# stokes_polarimeter_oled.net
KiCad netlist of a schematic drawn in EAGLE
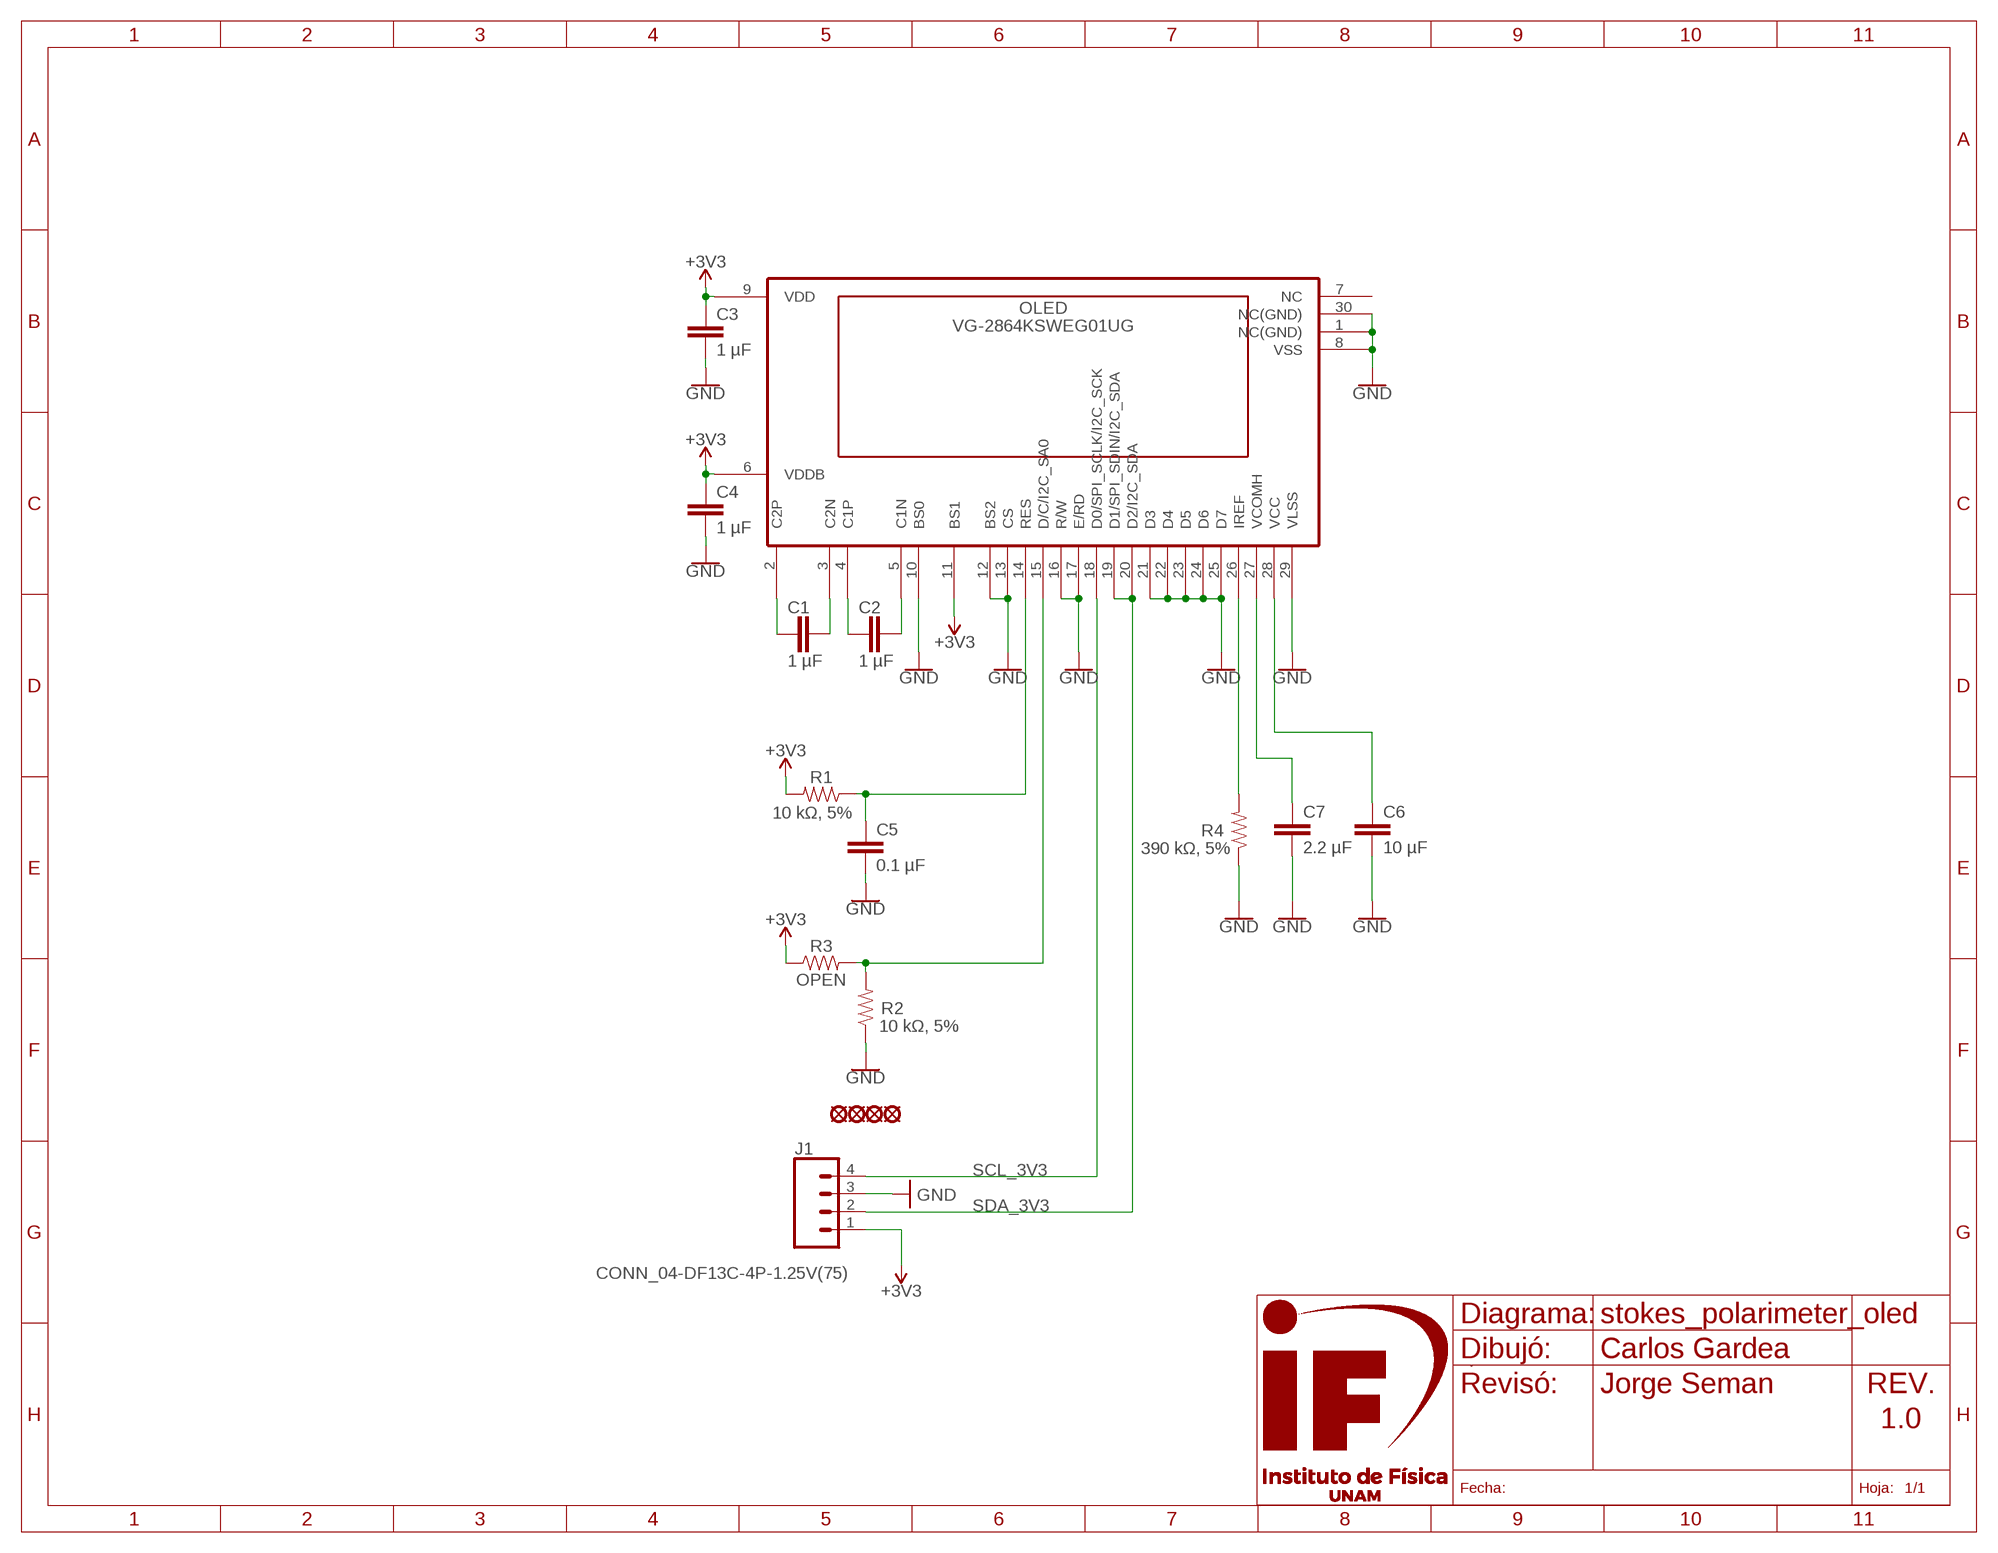
[diagram p0: schematic, sheet 1]

(export (version "E")
  (design (tool "Eeschema 10.0.6"))
  (components
    (comp (ref "C1")
      (value "1 µF")
      (footprint "eagle-import:C1206")
      (fields (field (name "MFR") "KEMET"))
      (libsource (lib "eagle-import") (part "1µF-C1206C105K3RACTU"))
    )
    (comp (ref "C2")
      (value "1 µF")
      (footprint "eagle-import:C1206")
      (fields (field (name "MFR") "KEMET"))
      (libsource (lib "eagle-import") (part "1µF-C1206C105K3RACTU"))
    )
    (comp (ref "C3")
      (value "1 µF")
      (footprint "eagle-import:C1206")
      (fields (field (name "MFR") "KEMET"))
      (libsource (lib "eagle-import") (part "1µF-C1206C105K3RACTU"))
    )
    (comp (ref "C4")
      (value "1 µF")
      (footprint "eagle-import:C1206")
      (fields (field (name "MFR") "KEMET"))
      (libsource (lib "eagle-import") (part "1µF-C1206C105K3RACTU"))
    )
    (comp (ref "C5")
      (value "0.1 µF")
      (footprint "eagle-import:C1206")
      (fields (field (name "MFR") "KEMET"))
      (libsource (lib "eagle-import") (part "0.1µF-C1206C104J1RACTU"))
    )
    (comp (ref "C6")
      (value "10 µF")
      (footprint "eagle-import:C1206")
      (fields (field (name "MFR") "KEMET"))
      (libsource (lib "eagle-import") (part "10µF-C1206C106K4PACTU"))
    )
    (comp (ref "C7")
      (value "2.2 µF")
      (footprint "eagle-import:C1206")
      (fields (field (name "MFR") "KEMET"))
      (libsource (lib "eagle-import") (part "2.2µF-C1206C225K4PACTU"))
    )
    (comp (ref "H5")
      (value "HOLE-M2.5")
      (footprint "eagle-import:HOLE_2.5")
      (libsource (lib "eagle-import") (part "HOLE-M2.5"))
    )
    (comp (ref "H6")
      (value "HOLE-M2.5")
      (footprint "eagle-import:HOLE_2.5")
      (libsource (lib "eagle-import") (part "HOLE-M2.5"))
    )
    (comp (ref "H7")
      (value "HOLE-M2.5")
      (footprint "eagle-import:HOLE_2.5")
      (libsource (lib "eagle-import") (part "HOLE-M2.5"))
    )
    (comp (ref "H8")
      (value "HOLE-M2.5")
      (footprint "eagle-import:HOLE_2.5")
      (libsource (lib "eagle-import") (part "HOLE-M2.5"))
    )
    (comp (ref "J1")
      (value "CONN_04-DF13C-4P-1.25V(75)")
      (footprint "eagle-import:DF13C4P125V")
      (fields (field (name "MFR") "Hirose Connector"))
      (libsource (lib "eagle-import") (part "CONN_04-DF13C-4P-1.25V(75)"))
    )
    (comp (ref "OLED")
      (value "VG-2864KSWEG01UG")
      (footprint "eagle-import:UG-2864HSWEG01")
      (libsource (lib "eagle-import") (part "VG-2864KSWEG01UG"))
    )
    (comp (ref "R1")
      (value "10 kΩ, 5%")
      (footprint "eagle-import:R1206")
      (fields (field (name "MFR") "Yageo"))
      (libsource (lib "eagle-import") (part "10KΩ-RC1206JR-0710KL"))
    )
    (comp (ref "R2")
      (value "10 kΩ, 5%")
      (footprint "eagle-import:R1206")
      (fields (field (name "MFR") "Yageo"))
      (libsource (lib "eagle-import") (part "10KΩ-RC1206JR-0710KL"))
    )
    (comp (ref "R3")
      (value "OPEN")
      (footprint "eagle-import:R1206_OPEN")
      (fields (field (name "MFR") "NA"))
      (libsource (lib "eagle-import") (part "OPEN"))
    )
    (comp (ref "R4")
      (value "390 kΩ, 5%")
      (footprint "eagle-import:R1206")
      (fields (field (name "MFR") "Yageo"))
      (libsource (lib "eagle-import") (part "390KΩ-RC1206JR-07390KL"))
    )
    (comp (ref "U$1")
      (value "IFUNAM_FRAME_LETTER_HNONE")
      (footprint "eagle-import:NONE")
      (fields
        (field (name "AUTHOR") "Carlos Gardea")
        (field (name "REVISOR") "Jorge Seman")
        (field (name "author") "author")
      )
      (libsource (lib "eagle-import") (part "IFUNAM_FRAME_LETTER_HNONE"))
    )
  )
  (nets
    (net (code "1") (name "+3V3") (class "Default")
      (node (ref "C3") (pin "1") (pinfunction "1_1") (pintype "passive"))
      (node (ref "C4") (pin "1") (pinfunction "1_1") (pintype "passive"))
      (node (ref "J1") (pin "1") (pinfunction "1_1") (pintype "passive"))
      (node (ref "OLED") (pin "11") (pinfunction "BS1_11") (pintype "passive"))
      (node (ref "OLED") (pin "6") (pinfunction "VDDB_6") (pintype "passive"))
      (node (ref "OLED") (pin "9") (pinfunction "VDD_9") (pintype "passive"))
      (node (ref "R1") (pin "2") (pinfunction "2_2") (pintype "passive"))
      (node (ref "R3") (pin "1") (pinfunction "1_1") (pintype "passive"))
    )
    (net (code "2") (name "/SCL_3V3") (class "Default")
      (node (ref "J1") (pin "4") (pinfunction "4_4") (pintype "passive"))
      (node (ref "OLED") (pin "18") (pinfunction "D0/SPI_SCLK/I2C_SCK_18") (pintype "passive"))
    )
    (net (code "3") (name "/SDA_3V3") (class "Default")
      (node (ref "J1") (pin "2") (pinfunction "2_2") (pintype "passive"))
      (node (ref "OLED") (pin "19") (pinfunction "D1/SPI_SDIN/I2C_SDA_19") (pintype "passive"))
      (node (ref "OLED") (pin "20") (pinfunction "D2/I2C_SDA_20") (pintype "passive"))
    )
    (net (code "4") (name "GND") (class "Default")
      (node (ref "C3") (pin "2") (pinfunction "2_2") (pintype "passive"))
      (node (ref "C4") (pin "2") (pinfunction "2_2") (pintype "passive"))
      (node (ref "C5") (pin "2") (pinfunction "2_2") (pintype "passive"))
      (node (ref "C6") (pin "2") (pinfunction "2_2") (pintype "passive"))
      (node (ref "C7") (pin "2") (pinfunction "2_2") (pintype "passive"))
      (node (ref "J1") (pin "3") (pinfunction "3_3") (pintype "passive"))
      (node (ref "OLED") (pin "1") (pinfunction "NC(GND)_1") (pintype "passive"))
      (node (ref "OLED") (pin "10") (pinfunction "BS0_10") (pintype "passive"))
      (node (ref "OLED") (pin "12") (pinfunction "BS2_12") (pintype "passive"))
      (node (ref "OLED") (pin "13") (pinfunction "CS_13") (pintype "passive"))
      (node (ref "OLED") (pin "16") (pinfunction "R/W_16") (pintype "passive"))
      (node (ref "OLED") (pin "17") (pinfunction "E/RD_17") (pintype "passive"))
      (node (ref "OLED") (pin "21") (pinfunction "D3_21") (pintype "passive"))
      (node (ref "OLED") (pin "22") (pinfunction "D4_22") (pintype "passive"))
      (node (ref "OLED") (pin "23") (pinfunction "D5_23") (pintype "passive"))
      (node (ref "OLED") (pin "24") (pinfunction "D6_24") (pintype "passive"))
      (node (ref "OLED") (pin "25") (pinfunction "D7_25") (pintype "passive"))
      (node (ref "OLED") (pin "29") (pinfunction "VLSS_29") (pintype "passive"))
      (node (ref "OLED") (pin "30") (pinfunction "NC(GND)_30") (pintype "passive"))
      (node (ref "OLED") (pin "8") (pinfunction "VSS_8") (pintype "passive"))
      (node (ref "R2") (pin "1") (pinfunction "1_1") (pintype "passive"))
      (node (ref "R4") (pin "1") (pinfunction "1_1") (pintype "passive"))
    )
    (net (code "5") (name "Net-(OLED-C1N)") (class "Default")
      (node (ref "C2") (pin "2") (pinfunction "2_2") (pintype "passive"))
      (node (ref "OLED") (pin "5") (pinfunction "C1N_5") (pintype "passive"))
    )
    (net (code "6") (name "Net-(OLED-C1P)") (class "Default")
      (node (ref "C2") (pin "1") (pinfunction "1_1") (pintype "passive"))
      (node (ref "OLED") (pin "4") (pinfunction "C1P_4") (pintype "passive"))
    )
    (net (code "7") (name "Net-(OLED-C2N)") (class "Default")
      (node (ref "C1") (pin "2") (pinfunction "2_2") (pintype "passive"))
      (node (ref "OLED") (pin "3") (pinfunction "C2N_3") (pintype "passive"))
    )
    (net (code "8") (name "Net-(OLED-C2P)") (class "Default")
      (node (ref "C1") (pin "1") (pinfunction "1_1") (pintype "passive"))
      (node (ref "OLED") (pin "2") (pinfunction "C2P_2") (pintype "passive"))
    )
    (net (code "9") (name "Net-(OLED-D{slash}C{slash}I2C_SA0)") (class "Default")
      (node (ref "OLED") (pin "15") (pinfunction "D/C/I2C_SA0_15") (pintype "passive"))
      (node (ref "R2") (pin "2") (pinfunction "2_2") (pintype "passive"))
      (node (ref "R3") (pin "2") (pinfunction "2_2") (pintype "passive"))
    )
    (net (code "10") (name "Net-(OLED-IREF)") (class "Default")
      (node (ref "OLED") (pin "26") (pinfunction "IREF_26") (pintype "passive"))
      (node (ref "R4") (pin "2") (pinfunction "2_2") (pintype "passive"))
    )
    (net (code "11") (name "Net-(OLED-RES)") (class "Default")
      (node (ref "C5") (pin "1") (pinfunction "1_1") (pintype "passive"))
      (node (ref "OLED") (pin "14") (pinfunction "RES_14") (pintype "passive"))
      (node (ref "R1") (pin "1") (pinfunction "1_1") (pintype "passive"))
    )
    (net (code "12") (name "Net-(OLED-VCC)") (class "Default")
      (node (ref "C6") (pin "1") (pinfunction "1_1") (pintype "passive"))
      (node (ref "OLED") (pin "28") (pinfunction "VCC_28") (pintype "passive"))
    )
    (net (code "13") (name "Net-(OLED-VCOMH)") (class "Default")
      (node (ref "C7") (pin "1") (pinfunction "1_1") (pintype "passive"))
      (node (ref "OLED") (pin "27") (pinfunction "VCOMH_27") (pintype "passive"))
    )
    (net (code "14") (name "unconnected-(OLED-NC-Pad7)") (class "Default")
      (node (ref "OLED") (pin "7") (pinfunction "NC_7") (pintype "passive"))
    )
  )
)
